# SO08-breakout.net
KiCad netlist of a schematic drawn in EAGLE
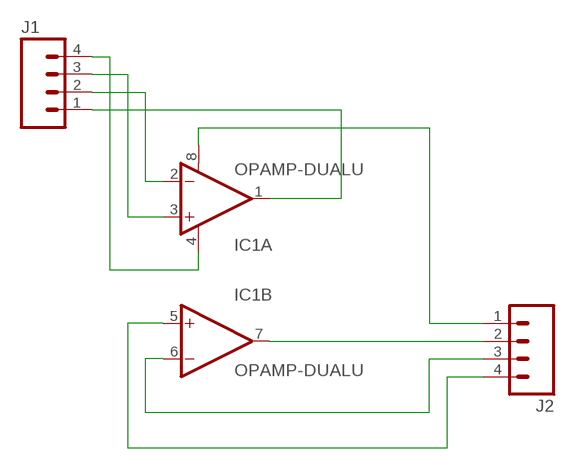
[diagram p0: schematic, sheet 1]

(export (version "E")
  (design (tool "Eeschema 10.0.6"))
  (components
    (comp (ref "IC1")
      (value "OPAMP-DUALU")
      (footprint "eagle-import:SO08")
      (libsource (lib "eagle-import") (part "OPAMP-DUALU"))
    )
    (comp (ref "J1")
      (value "M04PTH")
      (footprint "eagle-import:1X04")
      (libsource (lib "eagle-import") (part "M04PTH"))
    )
    (comp (ref "J2")
      (value "M04PTH")
      (footprint "eagle-import:1X04")
      (libsource (lib "eagle-import") (part "M04PTH"))
    )
  )
  (nets
    (net (code "1") (name "Net-(IC1A-+IN)") (class "Default")
      (node (ref "IC1") (pin "3") (pinfunction "+IN_3") (pintype "input"))
      (node (ref "J1") (pin "3") (pinfunction "3_3") (pintype "passive"))
    )
    (net (code "2") (name "Net-(IC1A--IN)") (class "Default")
      (node (ref "IC1") (pin "2") (pinfunction "-IN_2") (pintype "input"))
      (node (ref "J1") (pin "2") (pinfunction "2_2") (pintype "passive"))
    )
    (net (code "3") (name "Net-(IC1A-OUT)") (class "Default")
      (node (ref "IC1") (pin "1") (pinfunction "OUT_1") (pintype "output"))
      (node (ref "J1") (pin "1") (pinfunction "1_1") (pintype "passive"))
    )
    (net (code "4") (name "Net-(IC1A-V+)") (class "Default")
      (node (ref "IC1") (pin "8") (pinfunction "V+_8") (pintype "power_in"))
      (node (ref "J2") (pin "1") (pinfunction "1_1") (pintype "passive"))
    )
    (net (code "5") (name "Net-(IC1A-V-)") (class "Default")
      (node (ref "IC1") (pin "4") (pinfunction "V-_4") (pintype "power_in"))
      (node (ref "J1") (pin "4") (pinfunction "4_4") (pintype "passive"))
    )
    (net (code "6") (name "Net-(IC1B-+IN)") (class "Default")
      (node (ref "IC1") (pin "5") (pinfunction "+IN_5") (pintype "input"))
      (node (ref "J2") (pin "4") (pinfunction "4_4") (pintype "passive"))
    )
    (net (code "7") (name "Net-(IC1B--IN)") (class "Default")
      (node (ref "IC1") (pin "6") (pinfunction "-IN_6") (pintype "input"))
      (node (ref "J2") (pin "3") (pinfunction "3_3") (pintype "passive"))
    )
    (net (code "8") (name "Net-(IC1B-OUT)") (class "Default")
      (node (ref "IC1") (pin "7") (pinfunction "OUT_7") (pintype "output"))
      (node (ref "J2") (pin "2") (pinfunction "2_2") (pintype "passive"))
    )
  )
)
